# Expansion_board_rev1.net
KiCad netlist of a schematic drawn in EAGLE
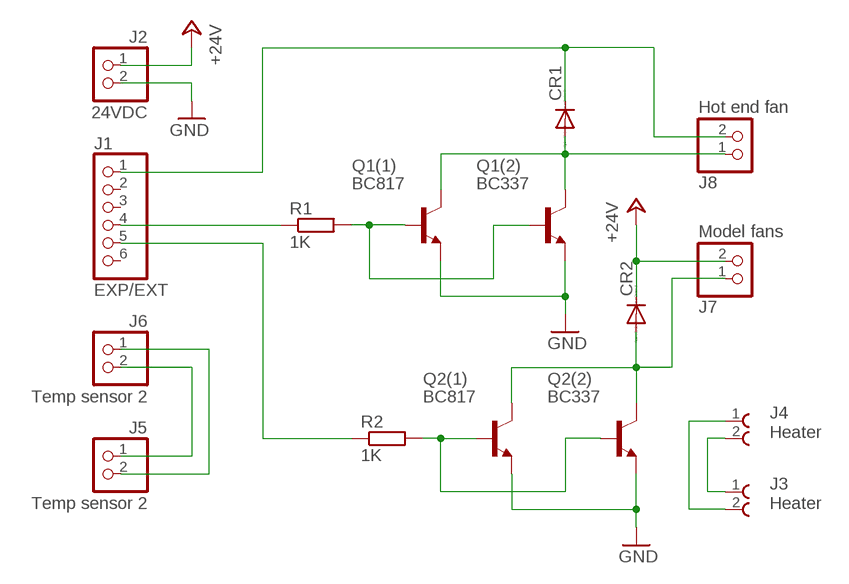
[diagram p0: schematic, sheet 1]

(export (version "E")
  (design (tool "Eeschema 10.0.6"))
  (components
    (comp (ref "CR1")
      (value "TESTDIODE")
      (footprint "eagle-import:DO214AC")
      (libsource (lib "eagle-import") (part "TESTDIODE"))
    )
    (comp (ref "CR2")
      (value "TESTDIODE")
      (footprint "eagle-import:DO214AC")
      (libsource (lib "eagle-import") (part "TESTDIODE"))
    )
    (comp (ref "J1")
      (value "EXP/EXT")
      (footprint "eagle-import:2X03")
      (libsource (lib "eagle-import") (part "PINHD-2X3"))
    )
    (comp (ref "J2")
      (value "24VDC")
      (footprint "eagle-import:1X02")
      (libsource (lib "eagle-import") (part "PINHD-1X2"))
    )
    (comp (ref "J3")
      (value "Heater")
      (footprint "eagle-import:691216710002")
      (libsource (lib "eagle-import") (part "691216710002"))
    )
    (comp (ref "J4")
      (value "Heater")
      (footprint "eagle-import:691216710002")
      (libsource (lib "eagle-import") (part "691216710002"))
    )
    (comp (ref "J5")
      (value "Temp sensor 2")
      (footprint "eagle-import:1X02")
      (libsource (lib "eagle-import") (part "PINHD-1X2"))
    )
    (comp (ref "J6")
      (value "Temp sensor 2")
      (footprint "eagle-import:1X02")
      (libsource (lib "eagle-import") (part "PINHD-1X2"))
    )
    (comp (ref "J7")
      (value "Model fans")
      (footprint "eagle-import:1X02")
      (libsource (lib "eagle-import") (part "PINHD-1X2"))
    )
    (comp (ref "J8")
      (value "Hot end fan")
      (footprint "eagle-import:JST_XH_2_RA")
      (libsource (lib "eagle-import") (part "S2B-XH-A"))
    )
    (comp (ref "Q1(1)")
      (value "BC817")
      (footprint "eagle-import:SOT23-BEC")
      (libsource (lib "eagle-import") (part "BC817SMD-40"))
    )
    (comp (ref "Q1(2)")
      (value "BC337")
      (footprint "eagle-import:TO92")
      (libsource (lib "eagle-import") (part "BC337-40"))
    )
    (comp (ref "Q2(1)")
      (value "BC817")
      (footprint "eagle-import:SOT23-BEC")
      (libsource (lib "eagle-import") (part "BC817SMD-40"))
    )
    (comp (ref "Q2(2)")
      (value "BC337")
      (footprint "eagle-import:TO92")
      (libsource (lib "eagle-import") (part "BC337-40"))
    )
    (comp (ref "R1")
      (value "1K")
      (footprint "eagle-import:M3216")
      (libsource (lib "eagle-import") (part "R-EU_M3216"))
    )
    (comp (ref "R2")
      (value "1K")
      (footprint "eagle-import:M3216")
      (libsource (lib "eagle-import") (part "R-EU_M3216"))
    )
  )
  (nets
    (net (code "1") (name "+24V") (class "Default")
      (node (ref "CR2") (pin "C") (pinfunction "C_C") (pintype "passive"))
      (node (ref "J2") (pin "1") (pinfunction "1_1") (pintype "passive"))
      (node (ref "J7") (pin "2") (pinfunction "2_2") (pintype "passive"))
    )
    (net (code "2") (name "GND") (class "Default")
      (node (ref "J2") (pin "2") (pinfunction "2_2") (pintype "passive"))
      (node (ref "Q1(1)") (pin "E") (pinfunction "E_E") (pintype "passive"))
      (node (ref "Q1(2)") (pin "1") (pinfunction "E_1") (pintype "passive"))
      (node (ref "Q2(1)") (pin "E") (pinfunction "E_E") (pintype "passive"))
      (node (ref "Q2(2)") (pin "1") (pinfunction "E_1") (pintype "passive"))
    )
    (net (code "3") (name "Net-(CR1-PadC)") (class "Default")
      (node (ref "CR1") (pin "C") (pinfunction "C_C") (pintype "passive"))
      (node (ref "J1") (pin "1") (pinfunction "1_1") (pintype "passive"))
      (node (ref "J8") (pin "2") (pinfunction "2_2") (pintype "passive"))
    )
    (net (code "4") (name "Net-(J1-Pad4)") (class "Default")
      (node (ref "J1") (pin "4") (pinfunction "4_4") (pintype "passive"))
      (node (ref "R1") (pin "1") (pinfunction "1_1") (pintype "passive"))
    )
    (net (code "5") (name "Net-(J1-Pad5)") (class "Default")
      (node (ref "J1") (pin "5") (pinfunction "5_5") (pintype "passive"))
      (node (ref "R2") (pin "1") (pinfunction "1_1") (pintype "passive"))
    )
    (net (code "6") (name "Net-(J3-Pad1)") (class "Default")
      (node (ref "J3") (pin "1") (pinfunction "1_1") (pintype "passive"))
      (node (ref "J4") (pin "2") (pinfunction "2_2") (pintype "passive"))
    )
    (net (code "7") (name "Net-(J3-Pad2)") (class "Default")
      (node (ref "J3") (pin "2") (pinfunction "2_2") (pintype "passive"))
      (node (ref "J4") (pin "1") (pinfunction "1_1") (pintype "passive"))
    )
    (net (code "8") (name "Net-(J5-Pad1)") (class "Default")
      (node (ref "J5") (pin "1") (pinfunction "1_1") (pintype "passive"))
      (node (ref "J6") (pin "2") (pinfunction "2_2") (pintype "passive"))
    )
    (net (code "9") (name "Net-(J5-Pad2)") (class "Default")
      (node (ref "J5") (pin "2") (pinfunction "2_2") (pintype "passive"))
      (node (ref "J6") (pin "1") (pinfunction "1_1") (pintype "passive"))
    )
    (net (code "10") (name "Net-(Q1(2)-B)") (class "Default")
      (node (ref "Q1(1)") (pin "B") (pinfunction "B_B") (pintype "passive"))
      (node (ref "Q1(2)") (pin "2") (pinfunction "B_2") (pintype "passive"))
      (node (ref "R1") (pin "2") (pinfunction "2_2") (pintype "passive"))
    )
    (net (code "11") (name "Net-(Q1(2)-C)") (class "Default")
      (node (ref "CR1") (pin "A") (pinfunction "A_A") (pintype "passive"))
      (node (ref "J8") (pin "1") (pinfunction "1_1") (pintype "passive"))
      (node (ref "Q1(1)") (pin "C") (pinfunction "C_C") (pintype "passive"))
      (node (ref "Q1(2)") (pin "3") (pinfunction "C_3") (pintype "passive"))
    )
    (net (code "12") (name "Net-(Q2(2)-B)") (class "Default")
      (node (ref "Q2(1)") (pin "B") (pinfunction "B_B") (pintype "passive"))
      (node (ref "Q2(2)") (pin "2") (pinfunction "B_2") (pintype "passive"))
      (node (ref "R2") (pin "2") (pinfunction "2_2") (pintype "passive"))
    )
    (net (code "13") (name "Net-(Q2(2)-C)") (class "Default")
      (node (ref "CR2") (pin "A") (pinfunction "A_A") (pintype "passive"))
      (node (ref "J7") (pin "1") (pinfunction "1_1") (pintype "passive"))
      (node (ref "Q2(1)") (pin "C") (pinfunction "C_C") (pintype "passive"))
      (node (ref "Q2(2)") (pin "3") (pinfunction "C_3") (pintype "passive"))
    )
    (net (code "14") (name "unconnected-(J1-Pad2)") (class "Default")
      (node (ref "J1") (pin "2") (pinfunction "2_2") (pintype "passive"))
    )
    (net (code "15") (name "unconnected-(J1-Pad3)") (class "Default")
      (node (ref "J1") (pin "3") (pinfunction "3_3") (pintype "passive"))
    )
    (net (code "16") (name "unconnected-(J1-Pad6)") (class "Default")
      (node (ref "J1") (pin "6") (pinfunction "6_6") (pintype "passive"))
    )
  )
)
